# gewaechshaus.net
KiCad netlist of a schematic drawn in EAGLE
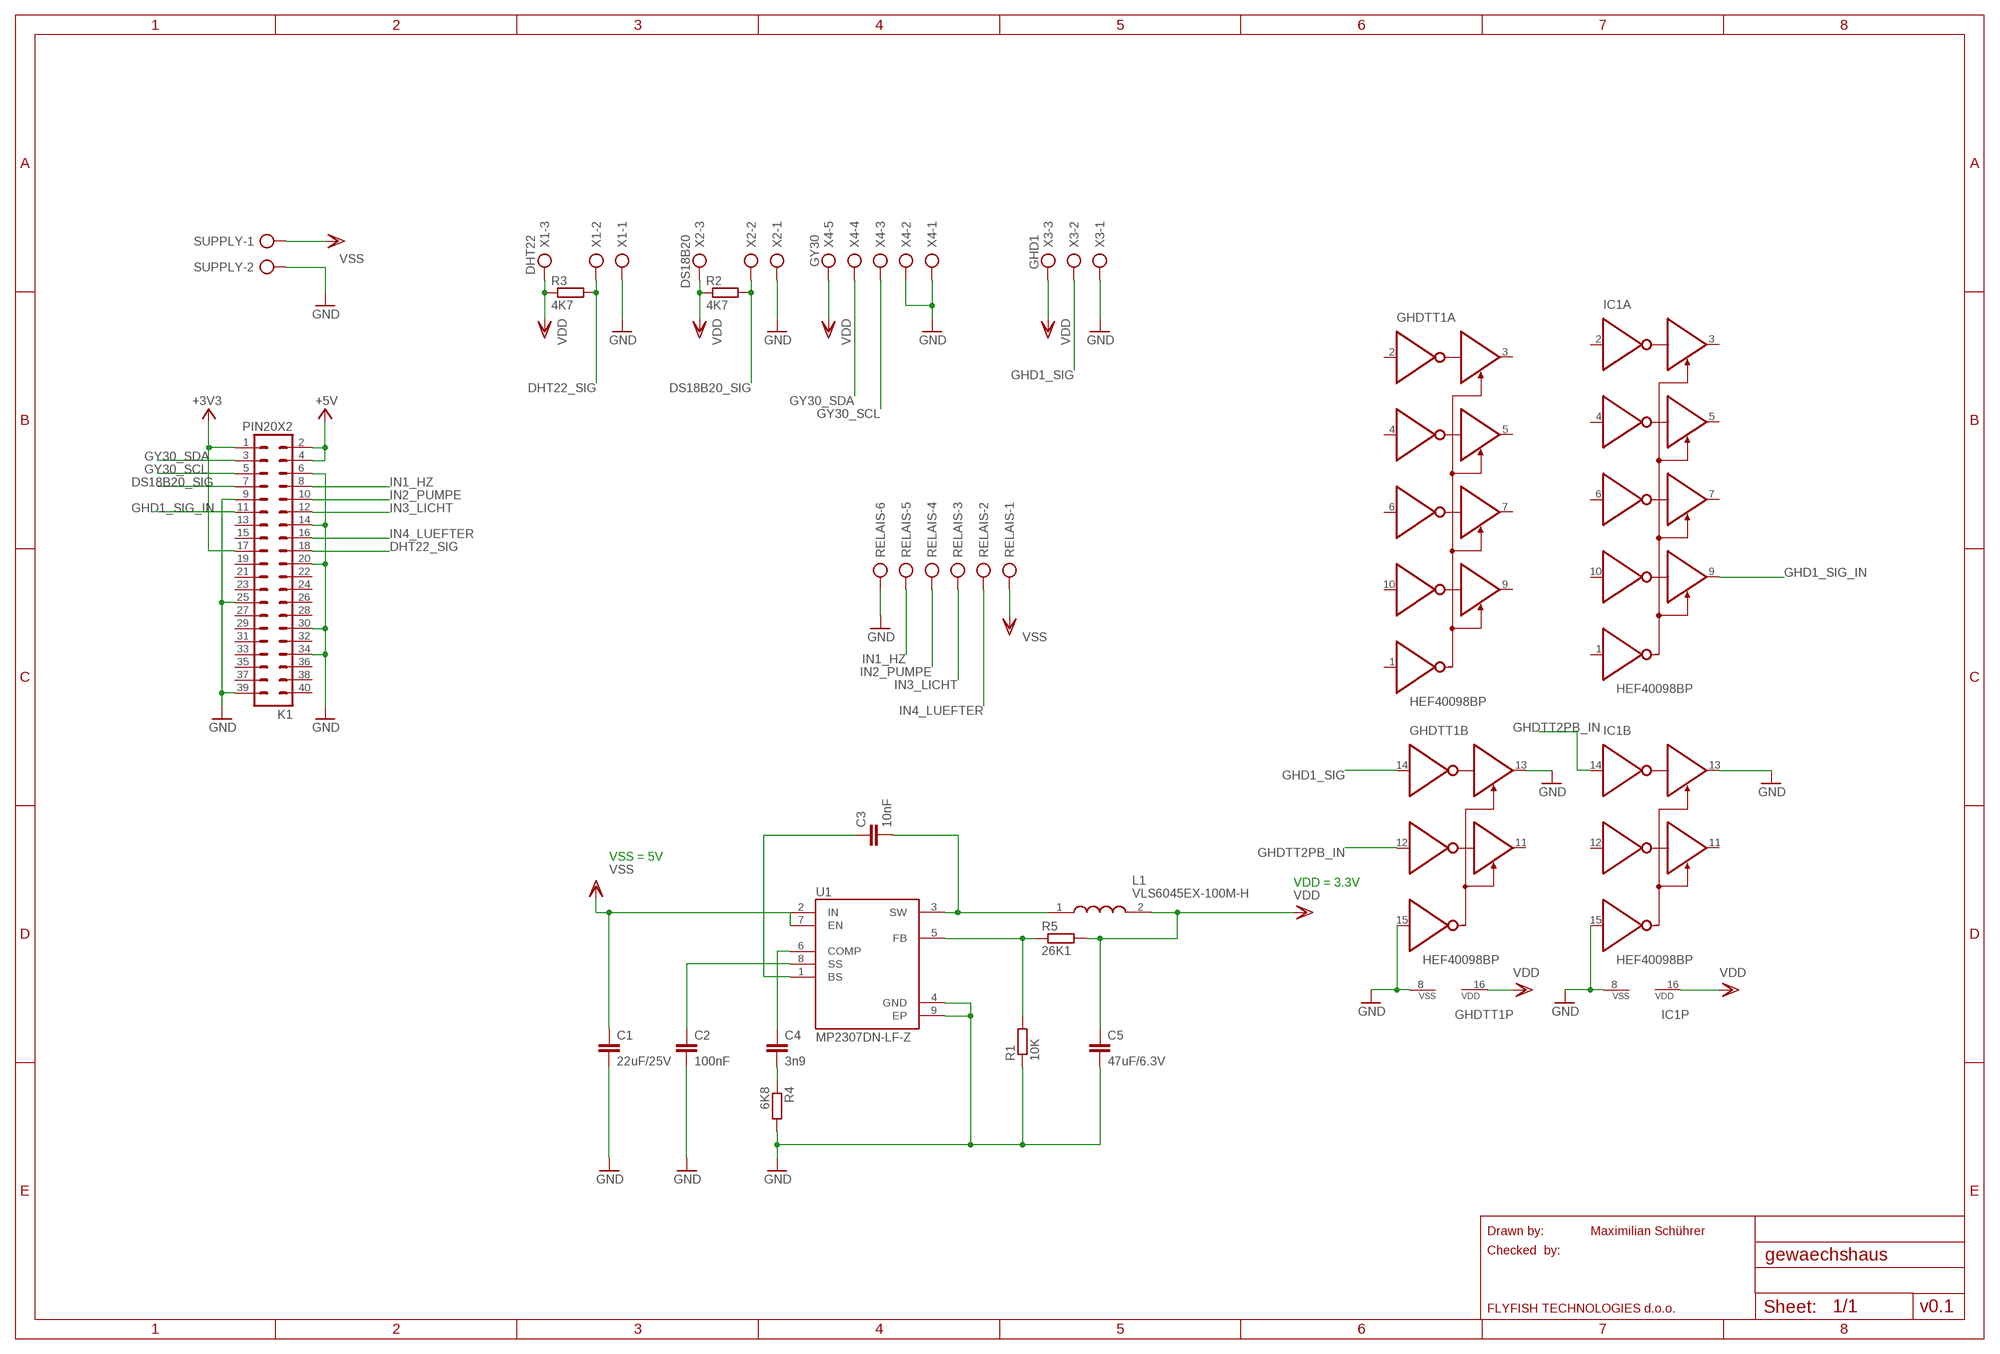
[diagram p0: schematic, sheet 1]

(export (version "E")
  (design (tool "Eeschema 10.0.6"))
  (components
    (comp (ref "C1")
      (value "22uF/25V")
      (footprint "eagle-import:C0805K")
      (libsource (lib "eagle-import") (part "C-EUC0805K"))
    )
    (comp (ref "C2")
      (value "100nF")
      (footprint "eagle-import:C0805K")
      (libsource (lib "eagle-import") (part "C-EUC0805K"))
    )
    (comp (ref "C3")
      (value "10nF")
      (footprint "eagle-import:C0805K")
      (libsource (lib "eagle-import") (part "C-EUC0805K"))
    )
    (comp (ref "C4")
      (value "3n9")
      (footprint "eagle-import:C0805K")
      (libsource (lib "eagle-import") (part "C-EUC0805K"))
    )
    (comp (ref "C5")
      (value "47uF/6.3V")
      (footprint "eagle-import:C0805K")
      (libsource (lib "eagle-import") (part "C-EUC0805K"))
    )
    (comp (ref "GHDTT1")
      (value "HEF40098BP")
      (footprint "eagle-import:DIL16")
      (libsource (lib "eagle-import") (part "HEF40098BP"))
    )
    (comp (ref "IC1")
      (value "HEF40098BP")
      (footprint "eagle-import:DIL16")
      (libsource (lib "eagle-import") (part "HEF40098BP"))
    )
    (comp (ref "K1")
      (value "PIN20X2")
      (footprint "eagle-import:PIN_20X2")
      (libsource (lib "eagle-import") (part "PIN20X2"))
    )
    (comp (ref "L1")
      (value "VLS6045EX-100M-H")
      (footprint "eagle-import:INDPM6360X450N")
      (fields (field (name "MOUSER_PART_NUMBER") "810-VLS6045EX-100M-H"))
      (libsource (lib "eagle-import") (part "VLS6045EX-100M-H"))
    )
    (comp (ref "R1")
      (value "10K")
      (footprint "eagle-import:R0805")
      (libsource (lib "eagle-import") (part "R-EU_R0805"))
    )
    (comp (ref "R2")
      (value "4K7")
      (footprint "eagle-import:R0805")
      (libsource (lib "eagle-import") (part "R-EU_R0805"))
    )
    (comp (ref "R3")
      (value "4K7")
      (footprint "eagle-import:R0805")
      (libsource (lib "eagle-import") (part "R-EU_R0805"))
    )
    (comp (ref "R4")
      (value "6K8")
      (footprint "eagle-import:R0805")
      (libsource (lib "eagle-import") (part "R-EU_R0805"))
    )
    (comp (ref "R5")
      (value "26K1")
      (footprint "eagle-import:R0805")
      (libsource (lib "eagle-import") (part "R-EU_R0805"))
    )
    (comp (ref "RELAIS")
      (value "AK500/6")
      (footprint "eagle-import:AK500_6")
      (libsource (lib "eagle-import") (part "AK500/6"))
    )
    (comp (ref "SUPPLY")
      (value "AK500/2")
      (footprint "eagle-import:AK500_2")
      (libsource (lib "eagle-import") (part "AK500/2"))
    )
    (comp (ref "U1")
      (value "MP2307DN-LF-Z")
      (footprint "eagle-import:SOIC127P600X170-9N")
      (fields (field (name "MF") "Monolithic Power"))
      (libsource (lib "eagle-import") (part "MP2307DN-LF-Z"))
    )
    (comp (ref "X1")
      (value "DHT22")
      (footprint "eagle-import:AK500_3")
      (libsource (lib "eagle-import") (part "AK500/3"))
    )
    (comp (ref "X2")
      (value "DS18B20")
      (footprint "eagle-import:AK500_3")
      (libsource (lib "eagle-import") (part "AK500/3"))
    )
    (comp (ref "X3")
      (value "GHD1")
      (footprint "eagle-import:AK500_3")
      (libsource (lib "eagle-import") (part "AK500/3"))
    )
    (comp (ref "X4")
      (value "GY30")
      (footprint "eagle-import:AK500_5")
      (libsource (lib "eagle-import") (part "AK500/5"))
    )
  )
  (nets
    (net (code "1") (name "+3V3") (class "Default")
      (node (ref "K1") (pin "1") (pinfunction "1_1") (pintype "passive"))
      (node (ref "K1") (pin "17") (pinfunction "17_17") (pintype "passive"))
    )
    (net (code "2") (name "+5V") (class "Default")
      (node (ref "K1") (pin "2") (pinfunction "2_2") (pintype "passive"))
      (node (ref "K1") (pin "4") (pinfunction "4_4") (pintype "passive"))
    )
    (net (code "3") (name "/DHT22_SIG") (class "Default")
      (node (ref "K1") (pin "18") (pinfunction "18_18") (pintype "passive"))
      (node (ref "R3") (pin "2") (pinfunction "2_2") (pintype "passive"))
      (node (ref "X1") (pin "2") (pinfunction "KL_2") (pintype "passive"))
    )
    (net (code "4") (name "/DS18B20_SIG") (class "Default")
      (node (ref "K1") (pin "7") (pinfunction "7_7") (pintype "passive"))
      (node (ref "R2") (pin "2") (pinfunction "2_2") (pintype "passive"))
      (node (ref "X2") (pin "2") (pinfunction "KL_2") (pintype "passive"))
    )
    (net (code "5") (name "/GHD1_SIG") (class "Default")
      (node (ref "GHDTT1") (pin "14") (pinfunction "2A0_14") (pintype "input"))
      (node (ref "X3") (pin "2") (pinfunction "KL_2") (pintype "passive"))
    )
    (net (code "6") (name "/GHD1_SIG_IN") (class "Default")
      (node (ref "IC1") (pin "9") (pinfunction "1Y3_9") (pintype "output"))
      (node (ref "K1") (pin "11") (pinfunction "11_11") (pintype "passive"))
    )
    (net (code "7") (name "/GHDTT2PB_IN") (class "Default")
      (node (ref "GHDTT1") (pin "12") (pinfunction "2A1_12") (pintype "input"))
      (node (ref "IC1") (pin "14") (pinfunction "2A0_14") (pintype "input"))
    )
    (net (code "8") (name "/GY30_SCL") (class "Default")
      (node (ref "K1") (pin "5") (pinfunction "5_5") (pintype "passive"))
      (node (ref "X4") (pin "3") (pinfunction "KL_3") (pintype "passive"))
    )
    (net (code "9") (name "/GY30_SDA") (class "Default")
      (node (ref "K1") (pin "3") (pinfunction "3_3") (pintype "passive"))
      (node (ref "X4") (pin "4") (pinfunction "KL_4") (pintype "passive"))
    )
    (net (code "10") (name "/IN1_HZ") (class "Default")
      (node (ref "K1") (pin "8") (pinfunction "8_8") (pintype "passive"))
      (node (ref "RELAIS") (pin "5") (pinfunction "KL_5") (pintype "passive"))
    )
    (net (code "11") (name "/IN2_PUMPE") (class "Default")
      (node (ref "K1") (pin "10") (pinfunction "10_10") (pintype "passive"))
      (node (ref "RELAIS") (pin "4") (pinfunction "KL_4") (pintype "passive"))
    )
    (net (code "12") (name "/IN3_LICHT") (class "Default")
      (node (ref "K1") (pin "12") (pinfunction "12_12") (pintype "passive"))
      (node (ref "RELAIS") (pin "3") (pinfunction "KL_3") (pintype "passive"))
    )
    (net (code "13") (name "/IN4_LUEFTER") (class "Default")
      (node (ref "K1") (pin "16") (pinfunction "16_16") (pintype "passive"))
      (node (ref "RELAIS") (pin "2") (pinfunction "KL_2") (pintype "passive"))
    )
    (net (code "14") (name "GND") (class "Default")
      (node (ref "C1") (pin "2") (pinfunction "2_2") (pintype "passive"))
      (node (ref "C2") (pin "2") (pinfunction "2_2") (pintype "passive"))
      (node (ref "C5") (pin "2") (pinfunction "2_2") (pintype "passive"))
      (node (ref "GHDTT1") (pin "13") (pinfunction "2Y0_13") (pintype "output"))
      (node (ref "GHDTT1") (pin "15") (pinfunction "2~{OE}_15") (pintype "input"))
      (node (ref "GHDTT1") (pin "8") (pinfunction "VSS_8") (pintype "power_in"))
      (node (ref "IC1") (pin "13") (pinfunction "2Y0_13") (pintype "output"))
      (node (ref "IC1") (pin "15") (pinfunction "2~{OE}_15") (pintype "input"))
      (node (ref "IC1") (pin "8") (pinfunction "VSS_8") (pintype "power_in"))
      (node (ref "K1") (pin "14") (pinfunction "14_14") (pintype "passive"))
      (node (ref "K1") (pin "20") (pinfunction "20_20") (pintype "passive"))
      (node (ref "K1") (pin "25") (pinfunction "25_25") (pintype "passive"))
      (node (ref "K1") (pin "30") (pinfunction "30_30") (pintype "passive"))
      (node (ref "K1") (pin "34") (pinfunction "34_34") (pintype "passive"))
      (node (ref "K1") (pin "39") (pinfunction "39_39") (pintype "passive"))
      (node (ref "K1") (pin "6") (pinfunction "6_6") (pintype "passive"))
      (node (ref "K1") (pin "9") (pinfunction "9_9") (pintype "passive"))
      (node (ref "R1") (pin "1") (pinfunction "1_1") (pintype "passive"))
      (node (ref "R4") (pin "2") (pinfunction "2_2") (pintype "passive"))
      (node (ref "RELAIS") (pin "6") (pinfunction "KL_6") (pintype "passive"))
      (node (ref "SUPPLY") (pin "2") (pinfunction "KL_2") (pintype "passive"))
      (node (ref "U1") (pin "4") (pinfunction "GND_4") (pintype "power_in"))
      (node (ref "U1") (pin "9") (pinfunction "EP_9") (pintype "power_in"))
      (node (ref "X1") (pin "1") (pinfunction "KL_1") (pintype "passive"))
      (node (ref "X2") (pin "1") (pinfunction "KL_1") (pintype "passive"))
      (node (ref "X3") (pin "1") (pinfunction "KL_1") (pintype "passive"))
      (node (ref "X4") (pin "1") (pinfunction "KL_1") (pintype "passive"))
      (node (ref "X4") (pin "2") (pinfunction "KL_2") (pintype "passive"))
    )
    (net (code "15") (name "Net-(C4-Pad2)") (class "Default")
      (node (ref "C4") (pin "2") (pinfunction "2_2") (pintype "passive"))
      (node (ref "R4") (pin "1") (pinfunction "1_1") (pintype "passive"))
    )
    (net (code "16") (name "Net-(U1-BS)") (class "Default")
      (node (ref "C3") (pin "1") (pinfunction "1_1") (pintype "passive"))
      (node (ref "U1") (pin "1") (pinfunction "BS_1") (pintype "passive"))
    )
    (net (code "17") (name "Net-(U1-COMP)") (class "Default")
      (node (ref "C4") (pin "1") (pinfunction "1_1") (pintype "passive"))
      (node (ref "U1") (pin "6") (pinfunction "COMP_6") (pintype "passive"))
    )
    (net (code "18") (name "Net-(U1-FB)") (class "Default")
      (node (ref "R1") (pin "2") (pinfunction "2_2") (pintype "passive"))
      (node (ref "R5") (pin "1") (pinfunction "1_1") (pintype "passive"))
      (node (ref "U1") (pin "5") (pinfunction "FB_5") (pintype "input"))
    )
    (net (code "19") (name "Net-(U1-SS)") (class "Default")
      (node (ref "C2") (pin "1") (pinfunction "1_1") (pintype "passive"))
      (node (ref "U1") (pin "8") (pinfunction "SS_8") (pintype "passive"))
    )
    (net (code "20") (name "Net-(U1-SW)") (class "Default")
      (node (ref "C3") (pin "2") (pinfunction "2_2") (pintype "passive"))
      (node (ref "L1") (pin "1") (pinfunction "1_1") (pintype "bidirectional"))
      (node (ref "U1") (pin "3") (pinfunction "SW_3") (pintype "output"))
    )
    (net (code "21") (name "VDD") (class "Default")
      (node (ref "C5") (pin "1") (pinfunction "1_1") (pintype "passive"))
      (node (ref "GHDTT1") (pin "16") (pinfunction "VDD_16") (pintype "power_in"))
      (node (ref "IC1") (pin "16") (pinfunction "VDD_16") (pintype "power_in"))
      (node (ref "L1") (pin "2") (pinfunction "2_2") (pintype "bidirectional"))
      (node (ref "R2") (pin "1") (pinfunction "1_1") (pintype "passive"))
      (node (ref "R3") (pin "1") (pinfunction "1_1") (pintype "passive"))
      (node (ref "R5") (pin "2") (pinfunction "2_2") (pintype "passive"))
      (node (ref "X1") (pin "3") (pinfunction "KL_3") (pintype "passive"))
      (node (ref "X2") (pin "3") (pinfunction "KL_3") (pintype "passive"))
      (node (ref "X3") (pin "3") (pinfunction "KL_3") (pintype "passive"))
      (node (ref "X4") (pin "5") (pinfunction "KL_5") (pintype "passive"))
    )
    (net (code "22") (name "VSS") (class "Default")
      (node (ref "C1") (pin "1") (pinfunction "1_1") (pintype "passive"))
      (node (ref "RELAIS") (pin "1") (pinfunction "KL_1") (pintype "passive"))
      (node (ref "SUPPLY") (pin "1") (pinfunction "KL_1") (pintype "passive"))
      (node (ref "U1") (pin "2") (pinfunction "IN_2") (pintype "input"))
      (node (ref "U1") (pin "7") (pinfunction "EN_7") (pintype "input"))
    )
    (net (code "23") (name "unconnected-(GHDTT1A-1A0-Pad2)") (class "Default")
      (node (ref "GHDTT1") (pin "2") (pinfunction "1A0_2") (pintype "input"))
    )
    (net (code "24") (name "unconnected-(GHDTT1A-1A1-Pad4)") (class "Default")
      (node (ref "GHDTT1") (pin "4") (pinfunction "1A1_4") (pintype "input"))
    )
    (net (code "25") (name "unconnected-(GHDTT1A-1A2-Pad6)") (class "Default")
      (node (ref "GHDTT1") (pin "6") (pinfunction "1A2_6") (pintype "input"))
    )
    (net (code "26") (name "unconnected-(GHDTT1A-1A3-Pad10)") (class "Default")
      (node (ref "GHDTT1") (pin "10") (pinfunction "1A3_10") (pintype "input"))
    )
    (net (code "27") (name "unconnected-(GHDTT1A-1Y0-Pad3)") (class "Default")
      (node (ref "GHDTT1") (pin "3") (pinfunction "1Y0_3") (pintype "output"))
    )
    (net (code "28") (name "unconnected-(GHDTT1A-1Y1-Pad5)") (class "Default")
      (node (ref "GHDTT1") (pin "5") (pinfunction "1Y1_5") (pintype "output"))
    )
    (net (code "29") (name "unconnected-(GHDTT1A-1Y2-Pad7)") (class "Default")
      (node (ref "GHDTT1") (pin "7") (pinfunction "1Y2_7") (pintype "output"))
    )
    (net (code "30") (name "unconnected-(GHDTT1A-1Y3-Pad9)") (class "Default")
      (node (ref "GHDTT1") (pin "9") (pinfunction "1Y3_9") (pintype "output"))
    )
    (net (code "31") (name "unconnected-(GHDTT1A-1~{OE}-Pad1)") (class "Default")
      (node (ref "GHDTT1") (pin "1") (pinfunction "1~{OE}_1") (pintype "input"))
    )
    (net (code "32") (name "unconnected-(GHDTT1B-2Y1-Pad11)") (class "Default")
      (node (ref "GHDTT1") (pin "11") (pinfunction "2Y1_11") (pintype "output"))
    )
    (net (code "33") (name "unconnected-(IC1A-1A0-Pad2)") (class "Default")
      (node (ref "IC1") (pin "2") (pinfunction "1A0_2") (pintype "input"))
    )
    (net (code "34") (name "unconnected-(IC1A-1A1-Pad4)") (class "Default")
      (node (ref "IC1") (pin "4") (pinfunction "1A1_4") (pintype "input"))
    )
    (net (code "35") (name "unconnected-(IC1A-1A2-Pad6)") (class "Default")
      (node (ref "IC1") (pin "6") (pinfunction "1A2_6") (pintype "input"))
    )
    (net (code "36") (name "unconnected-(IC1A-1A3-Pad10)") (class "Default")
      (node (ref "IC1") (pin "10") (pinfunction "1A3_10") (pintype "input"))
    )
    (net (code "37") (name "unconnected-(IC1A-1Y0-Pad3)") (class "Default")
      (node (ref "IC1") (pin "3") (pinfunction "1Y0_3") (pintype "output"))
    )
    (net (code "38") (name "unconnected-(IC1A-1Y1-Pad5)") (class "Default")
      (node (ref "IC1") (pin "5") (pinfunction "1Y1_5") (pintype "output"))
    )
    (net (code "39") (name "unconnected-(IC1A-1Y2-Pad7)") (class "Default")
      (node (ref "IC1") (pin "7") (pinfunction "1Y2_7") (pintype "output"))
    )
    (net (code "40") (name "unconnected-(IC1A-1~{OE}-Pad1)") (class "Default")
      (node (ref "IC1") (pin "1") (pinfunction "1~{OE}_1") (pintype "input"))
    )
    (net (code "41") (name "unconnected-(IC1B-2A1-Pad12)") (class "Default")
      (node (ref "IC1") (pin "12") (pinfunction "2A1_12") (pintype "input"))
    )
    (net (code "42") (name "unconnected-(IC1B-2Y1-Pad11)") (class "Default")
      (node (ref "IC1") (pin "11") (pinfunction "2Y1_11") (pintype "output"))
    )
    (net (code "43") (name "unconnected-(K1-Pad13)") (class "Default")
      (node (ref "K1") (pin "13") (pinfunction "13_13") (pintype "passive"))
    )
    (net (code "44") (name "unconnected-(K1-Pad15)") (class "Default")
      (node (ref "K1") (pin "15") (pinfunction "15_15") (pintype "passive"))
    )
    (net (code "45") (name "unconnected-(K1-Pad19)") (class "Default")
      (node (ref "K1") (pin "19") (pinfunction "19_19") (pintype "passive"))
    )
    (net (code "46") (name "unconnected-(K1-Pad21)") (class "Default")
      (node (ref "K1") (pin "21") (pinfunction "21_21") (pintype "passive"))
    )
    (net (code "47") (name "unconnected-(K1-Pad22)") (class "Default")
      (node (ref "K1") (pin "22") (pinfunction "22_22") (pintype "passive"))
    )
    (net (code "48") (name "unconnected-(K1-Pad23)") (class "Default")
      (node (ref "K1") (pin "23") (pinfunction "23_23") (pintype "passive"))
    )
    (net (code "49") (name "unconnected-(K1-Pad24)") (class "Default")
      (node (ref "K1") (pin "24") (pinfunction "24_24") (pintype "passive"))
    )
    (net (code "50") (name "unconnected-(K1-Pad26)") (class "Default")
      (node (ref "K1") (pin "26") (pinfunction "26_26") (pintype "passive"))
    )
    (net (code "51") (name "unconnected-(K1-Pad27)") (class "Default")
      (node (ref "K1") (pin "27") (pinfunction "27_27") (pintype "passive"))
    )
    (net (code "52") (name "unconnected-(K1-Pad28)") (class "Default")
      (node (ref "K1") (pin "28") (pinfunction "28_28") (pintype "passive"))
    )
    (net (code "53") (name "unconnected-(K1-Pad29)") (class "Default")
      (node (ref "K1") (pin "29") (pinfunction "29_29") (pintype "passive"))
    )
    (net (code "54") (name "unconnected-(K1-Pad31)") (class "Default")
      (node (ref "K1") (pin "31") (pinfunction "31_31") (pintype "passive"))
    )
    (net (code "55") (name "unconnected-(K1-Pad32)") (class "Default")
      (node (ref "K1") (pin "32") (pinfunction "32_32") (pintype "passive"))
    )
    (net (code "56") (name "unconnected-(K1-Pad33)") (class "Default")
      (node (ref "K1") (pin "33") (pinfunction "33_33") (pintype "passive"))
    )
    (net (code "57") (name "unconnected-(K1-Pad35)") (class "Default")
      (node (ref "K1") (pin "35") (pinfunction "35_35") (pintype "passive"))
    )
    (net (code "58") (name "unconnected-(K1-Pad36)") (class "Default")
      (node (ref "K1") (pin "36") (pinfunction "36_36") (pintype "passive"))
    )
    (net (code "59") (name "unconnected-(K1-Pad37)") (class "Default")
      (node (ref "K1") (pin "37") (pinfunction "37_37") (pintype "passive"))
    )
    (net (code "60") (name "unconnected-(K1-Pad38)") (class "Default")
      (node (ref "K1") (pin "38") (pinfunction "38_38") (pintype "passive"))
    )
    (net (code "61") (name "unconnected-(K1-Pad40)") (class "Default")
      (node (ref "K1") (pin "40") (pinfunction "40_40") (pintype "passive"))
    )
  )
)
